# FIT_CONN.net
KiCad netlist of a schematic drawn in Altium Designer
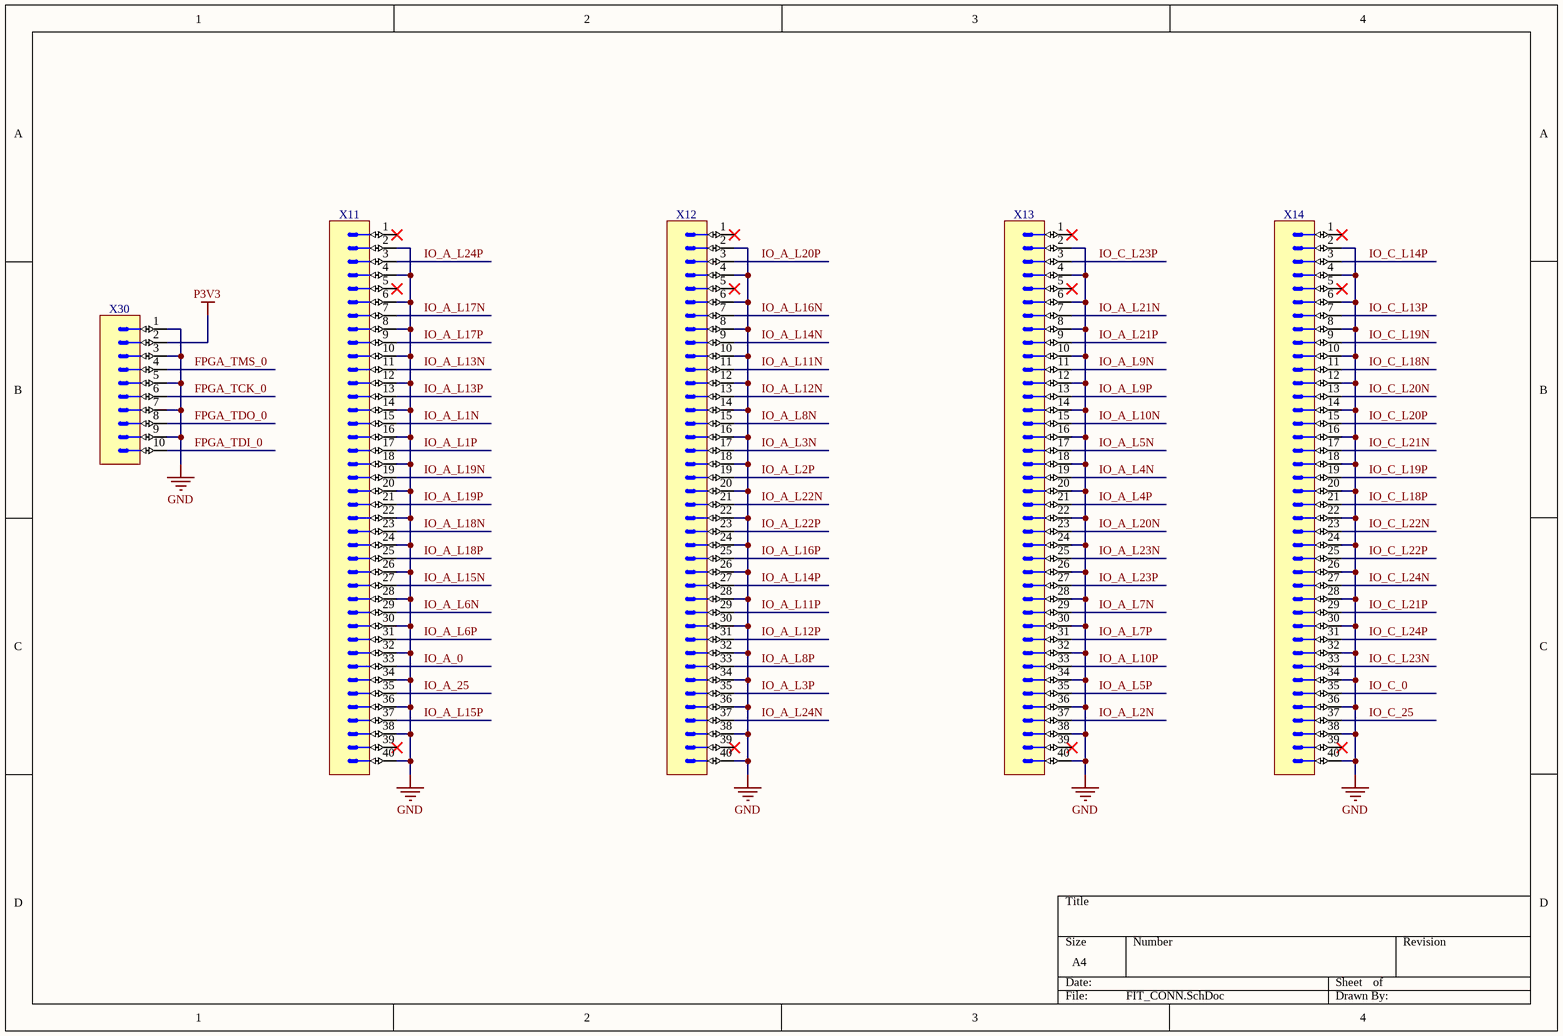
[diagram p0: FIT_CONN.SchDoc]

(export (version "E")
  (design (tool "Eeschema 10.0.6"))
  (components
    (comp (ref "X11")
      (value "~")
      (footprint "CONNFLY_DS1013-40SSIB1-B-0")
      (description "Connector 40 Male")
      (fields
        (field (name "PART NUMBER") "CONNFLY_DS1013-40SSIB1-B-0")
        (field (name "MANUFACTURER") "CONNFLY")
        (field (name "AUTHOR") "CERN DEM HF")
      )
      (libsource (lib "Connectors") (part "Connector 40 Male"))
    )
    (comp (ref "X12")
      (value "~")
      (footprint "CONNFLY_DS1013-40SSIB1-B-0")
      (description "Connector 40 Male")
      (fields
        (field (name "PART NUMBER") "CONNFLY_DS1013-40SSIB1-B-0")
        (field (name "MANUFACTURER") "CONNFLY")
        (field (name "AUTHOR") "CERN DEM HF")
      )
      (libsource (lib "Connectors") (part "Connector 40 Male"))
    )
    (comp (ref "X13")
      (value "~")
      (footprint "CONNFLY_DS1013-40SSIB1-B-0")
      (description "Connector 40 Male")
      (fields
        (field (name "PART NUMBER") "CONNFLY_DS1013-40SSIB1-B-0")
        (field (name "MANUFACTURER") "CONNFLY")
        (field (name "AUTHOR") "CERN DEM HF")
      )
      (libsource (lib "Connectors") (part "Connector 40 Male"))
    )
    (comp (ref "X14")
      (value "~")
      (footprint "CONNFLY_DS1013-40SSIB1-B-0")
      (description "Connector 40 Male")
      (fields
        (field (name "PART NUMBER") "CONNFLY_DS1013-40SSIB1-B-0")
        (field (name "MANUFACTURER") "CONNFLY")
        (field (name "AUTHOR") "CERN DEM HF")
      )
      (libsource (lib "Connectors") (part "Connector 40 Male"))
    )
    (comp (ref "X30")
      (value "~")
      (footprint "CONNFLY_DS1014-10SF1B-B")
      (description "Connector 10 Male")
      (fields
        (field (name "PART NUMBER") "CONNFLY_DS1014-10SF1B-B")
        (field (name "MANUFACTURER") "CONNFLY")
        (field (name "AUTHOR") "CERN DEM HF")
      )
      (libsource (lib "Connectors") (part "Connector 10 Male"))
    )
  )
  (nets
    (net (code "1") (name "/FPGA_TCK_0") (class "Default")
      (node (ref "X30") (pin "6") (pinfunction "6_6") (pintype "bidirectional"))
    )
    (net (code "2") (name "/FPGA_TDI_0") (class "Default")
      (node (ref "X30") (pin "10") (pinfunction "10_10") (pintype "bidirectional"))
    )
    (net (code "3") (name "/FPGA_TDO_0") (class "Default")
      (node (ref "X30") (pin "8") (pinfunction "8_8") (pintype "bidirectional"))
    )
    (net (code "4") (name "/FPGA_TMS_0") (class "Default")
      (node (ref "X30") (pin "4") (pinfunction "4_4") (pintype "bidirectional"))
    )
    (net (code "5") (name "/IO_A_0") (class "Default")
      (node (ref "X11") (pin "33") (pinfunction "33_33") (pintype "bidirectional"))
    )
    (net (code "6") (name "/IO_A_25") (class "Default")
      (node (ref "X11") (pin "35") (pinfunction "35_35") (pintype "bidirectional"))
    )
    (net (code "7") (name "/IO_A_L1N") (class "Default")
      (node (ref "X11") (pin "15") (pinfunction "15_15") (pintype "bidirectional"))
    )
    (net (code "8") (name "/IO_A_L1P") (class "Default")
      (node (ref "X11") (pin "17") (pinfunction "17_17") (pintype "bidirectional"))
    )
    (net (code "9") (name "/IO_A_L2N") (class "Default")
      (node (ref "X13") (pin "37") (pinfunction "37_37") (pintype "bidirectional"))
    )
    (net (code "10") (name "/IO_A_L2P") (class "Default")
      (node (ref "X12") (pin "19") (pinfunction "19_19") (pintype "bidirectional"))
    )
    (net (code "11") (name "/IO_A_L3N") (class "Default")
      (node (ref "X12") (pin "17") (pinfunction "17_17") (pintype "bidirectional"))
    )
    (net (code "12") (name "/IO_A_L3P") (class "Default")
      (node (ref "X12") (pin "35") (pinfunction "35_35") (pintype "bidirectional"))
    )
    (net (code "13") (name "/IO_A_L4N") (class "Default")
      (node (ref "X13") (pin "19") (pinfunction "19_19") (pintype "bidirectional"))
    )
    (net (code "14") (name "/IO_A_L4P") (class "Default")
      (node (ref "X13") (pin "21") (pinfunction "21_21") (pintype "bidirectional"))
    )
    (net (code "15") (name "/IO_A_L5N") (class "Default")
      (node (ref "X13") (pin "17") (pinfunction "17_17") (pintype "bidirectional"))
    )
    (net (code "16") (name "/IO_A_L5P") (class "Default")
      (node (ref "X13") (pin "35") (pinfunction "35_35") (pintype "bidirectional"))
    )
    (net (code "17") (name "/IO_A_L6N") (class "Default")
      (node (ref "X11") (pin "29") (pinfunction "29_29") (pintype "bidirectional"))
    )
    (net (code "18") (name "/IO_A_L6P") (class "Default")
      (node (ref "X11") (pin "31") (pinfunction "31_31") (pintype "bidirectional"))
    )
    (net (code "19") (name "/IO_A_L7N") (class "Default")
      (node (ref "X13") (pin "29") (pinfunction "29_29") (pintype "bidirectional"))
    )
    (net (code "20") (name "/IO_A_L7P") (class "Default")
      (node (ref "X13") (pin "31") (pinfunction "31_31") (pintype "bidirectional"))
    )
    (net (code "21") (name "/IO_A_L8N") (class "Default")
      (node (ref "X12") (pin "15") (pinfunction "15_15") (pintype "bidirectional"))
    )
    (net (code "22") (name "/IO_A_L8P") (class "Default")
      (node (ref "X12") (pin "33") (pinfunction "33_33") (pintype "bidirectional"))
    )
    (net (code "23") (name "/IO_A_L9N") (class "Default")
      (node (ref "X13") (pin "11") (pinfunction "11_11") (pintype "bidirectional"))
    )
    (net (code "24") (name "/IO_A_L9P") (class "Default")
      (node (ref "X13") (pin "13") (pinfunction "13_13") (pintype "bidirectional"))
    )
    (net (code "25") (name "/IO_A_L10N") (class "Default")
      (node (ref "X13") (pin "15") (pinfunction "15_15") (pintype "bidirectional"))
    )
    (net (code "26") (name "/IO_A_L10P") (class "Default")
      (node (ref "X13") (pin "33") (pinfunction "33_33") (pintype "bidirectional"))
    )
    (net (code "27") (name "/IO_A_L11N") (class "Default")
      (node (ref "X12") (pin "11") (pinfunction "11_11") (pintype "bidirectional"))
    )
    (net (code "28") (name "/IO_A_L11P") (class "Default")
      (node (ref "X12") (pin "29") (pinfunction "29_29") (pintype "bidirectional"))
    )
    (net (code "29") (name "/IO_A_L12N") (class "Default")
      (node (ref "X12") (pin "13") (pinfunction "13_13") (pintype "bidirectional"))
    )
    (net (code "30") (name "/IO_A_L12P") (class "Default")
      (node (ref "X12") (pin "31") (pinfunction "31_31") (pintype "bidirectional"))
    )
    (net (code "31") (name "/IO_A_L13N") (class "Default")
      (node (ref "X11") (pin "11") (pinfunction "11_11") (pintype "bidirectional"))
    )
    (net (code "32") (name "/IO_A_L13P") (class "Default")
      (node (ref "X11") (pin "13") (pinfunction "13_13") (pintype "bidirectional"))
    )
    (net (code "33") (name "/IO_A_L14N") (class "Default")
      (node (ref "X12") (pin "9") (pinfunction "9_9") (pintype "bidirectional"))
    )
    (net (code "34") (name "/IO_A_L14P") (class "Default")
      (node (ref "X12") (pin "27") (pinfunction "27_27") (pintype "bidirectional"))
    )
    (net (code "35") (name "/IO_A_L15N") (class "Default")
      (node (ref "X11") (pin "27") (pinfunction "27_27") (pintype "bidirectional"))
    )
    (net (code "36") (name "/IO_A_L15P") (class "Default")
      (node (ref "X11") (pin "37") (pinfunction "37_37") (pintype "bidirectional"))
    )
    (net (code "37") (name "/IO_A_L16N") (class "Default")
      (node (ref "X12") (pin "7") (pinfunction "7_7") (pintype "bidirectional"))
    )
    (net (code "38") (name "/IO_A_L16P") (class "Default")
      (node (ref "X12") (pin "25") (pinfunction "25_25") (pintype "bidirectional"))
    )
    (net (code "39") (name "/IO_A_L17N") (class "Default")
      (node (ref "X11") (pin "7") (pinfunction "7_7") (pintype "bidirectional"))
    )
    (net (code "40") (name "/IO_A_L17P") (class "Default")
      (node (ref "X11") (pin "9") (pinfunction "9_9") (pintype "bidirectional"))
    )
    (net (code "41") (name "/IO_A_L18N") (class "Default")
      (node (ref "X11") (pin "23") (pinfunction "23_23") (pintype "bidirectional"))
    )
    (net (code "42") (name "/IO_A_L18P") (class "Default")
      (node (ref "X11") (pin "25") (pinfunction "25_25") (pintype "bidirectional"))
    )
    (net (code "43") (name "/IO_A_L19N") (class "Default")
      (node (ref "X11") (pin "19") (pinfunction "19_19") (pintype "bidirectional"))
    )
    (net (code "44") (name "/IO_A_L19P") (class "Default")
      (node (ref "X11") (pin "21") (pinfunction "21_21") (pintype "bidirectional"))
    )
    (net (code "45") (name "/IO_A_L20N") (class "Default")
      (node (ref "X13") (pin "23") (pinfunction "23_23") (pintype "bidirectional"))
    )
    (net (code "46") (name "/IO_A_L20P") (class "Default")
      (node (ref "X12") (pin "3") (pinfunction "3_3") (pintype "bidirectional"))
    )
    (net (code "47") (name "/IO_A_L21N") (class "Default")
      (node (ref "X13") (pin "7") (pinfunction "7_7") (pintype "bidirectional"))
    )
    (net (code "48") (name "/IO_A_L21P") (class "Default")
      (node (ref "X13") (pin "9") (pinfunction "9_9") (pintype "bidirectional"))
    )
    (net (code "49") (name "/IO_A_L22N") (class "Default")
      (node (ref "X12") (pin "21") (pinfunction "21_21") (pintype "bidirectional"))
    )
    (net (code "50") (name "/IO_A_L22P") (class "Default")
      (node (ref "X12") (pin "23") (pinfunction "23_23") (pintype "bidirectional"))
    )
    (net (code "51") (name "/IO_A_L23N") (class "Default")
      (node (ref "X13") (pin "25") (pinfunction "25_25") (pintype "bidirectional"))
    )
    (net (code "52") (name "/IO_A_L23P") (class "Default")
      (node (ref "X13") (pin "27") (pinfunction "27_27") (pintype "bidirectional"))
    )
    (net (code "53") (name "/IO_A_L24N") (class "Default")
      (node (ref "X12") (pin "37") (pinfunction "37_37") (pintype "bidirectional"))
    )
    (net (code "54") (name "/IO_A_L24P") (class "Default")
      (node (ref "X11") (pin "3") (pinfunction "3_3") (pintype "bidirectional"))
    )
    (net (code "55") (name "/IO_C_0") (class "Default")
      (node (ref "X14") (pin "35") (pinfunction "35_35") (pintype "bidirectional"))
    )
    (net (code "56") (name "/IO_C_25") (class "Default")
      (node (ref "X14") (pin "37") (pinfunction "37_37") (pintype "bidirectional"))
    )
    (net (code "57") (name "/IO_C_L13P") (class "Default")
      (node (ref "X14") (pin "7") (pinfunction "7_7") (pintype "bidirectional"))
    )
    (net (code "58") (name "/IO_C_L14P") (class "Default")
      (node (ref "X14") (pin "3") (pinfunction "3_3") (pintype "bidirectional"))
    )
    (net (code "59") (name "/IO_C_L18N") (class "Default")
      (node (ref "X14") (pin "11") (pinfunction "11_11") (pintype "bidirectional"))
    )
    (net (code "60") (name "/IO_C_L18P") (class "Default")
      (node (ref "X14") (pin "21") (pinfunction "21_21") (pintype "bidirectional"))
    )
    (net (code "61") (name "/IO_C_L19N") (class "Default")
      (node (ref "X14") (pin "9") (pinfunction "9_9") (pintype "bidirectional"))
    )
    (net (code "62") (name "/IO_C_L19P") (class "Default")
      (node (ref "X14") (pin "19") (pinfunction "19_19") (pintype "bidirectional"))
    )
    (net (code "63") (name "/IO_C_L20N") (class "Default")
      (node (ref "X14") (pin "13") (pinfunction "13_13") (pintype "bidirectional"))
    )
    (net (code "64") (name "/IO_C_L20P") (class "Default")
      (node (ref "X14") (pin "15") (pinfunction "15_15") (pintype "bidirectional"))
    )
    (net (code "65") (name "/IO_C_L21N") (class "Default")
      (node (ref "X14") (pin "17") (pinfunction "17_17") (pintype "bidirectional"))
    )
    (net (code "66") (name "/IO_C_L21P") (class "Default")
      (node (ref "X14") (pin "29") (pinfunction "29_29") (pintype "bidirectional"))
    )
    (net (code "67") (name "/IO_C_L22N") (class "Default")
      (node (ref "X14") (pin "23") (pinfunction "23_23") (pintype "bidirectional"))
    )
    (net (code "68") (name "/IO_C_L22P") (class "Default")
      (node (ref "X14") (pin "25") (pinfunction "25_25") (pintype "bidirectional"))
    )
    (net (code "69") (name "/IO_C_L23N") (class "Default")
      (node (ref "X14") (pin "33") (pinfunction "33_33") (pintype "bidirectional"))
    )
    (net (code "70") (name "/IO_C_L23P") (class "Default")
      (node (ref "X13") (pin "3") (pinfunction "3_3") (pintype "bidirectional"))
    )
    (net (code "71") (name "/IO_C_L24N") (class "Default")
      (node (ref "X14") (pin "27") (pinfunction "27_27") (pintype "bidirectional"))
    )
    (net (code "72") (name "/IO_C_L24P") (class "Default")
      (node (ref "X14") (pin "31") (pinfunction "31_31") (pintype "bidirectional"))
    )
    (net (code "73") (name "GND") (class "Default")
      (node (ref "X11") (pin "10") (pinfunction "10_10") (pintype "bidirectional"))
      (node (ref "X11") (pin "12") (pinfunction "12_12") (pintype "bidirectional"))
      (node (ref "X11") (pin "14") (pinfunction "14_14") (pintype "bidirectional"))
      (node (ref "X11") (pin "16") (pinfunction "16_16") (pintype "bidirectional"))
      (node (ref "X11") (pin "18") (pinfunction "18_18") (pintype "bidirectional"))
      (node (ref "X11") (pin "2") (pinfunction "2_2") (pintype "bidirectional"))
      (node (ref "X11") (pin "20") (pinfunction "20_20") (pintype "bidirectional"))
      (node (ref "X11") (pin "22") (pinfunction "22_22") (pintype "bidirectional"))
      (node (ref "X11") (pin "24") (pinfunction "24_24") (pintype "bidirectional"))
      (node (ref "X11") (pin "26") (pinfunction "26_26") (pintype "bidirectional"))
      (node (ref "X11") (pin "28") (pinfunction "28_28") (pintype "bidirectional"))
      (node (ref "X11") (pin "30") (pinfunction "30_30") (pintype "bidirectional"))
      (node (ref "X11") (pin "32") (pinfunction "32_32") (pintype "bidirectional"))
      (node (ref "X11") (pin "34") (pinfunction "34_34") (pintype "bidirectional"))
      (node (ref "X11") (pin "36") (pinfunction "36_36") (pintype "bidirectional"))
      (node (ref "X11") (pin "38") (pinfunction "38_38") (pintype "bidirectional"))
      (node (ref "X11") (pin "4") (pinfunction "4_4") (pintype "bidirectional"))
      (node (ref "X11") (pin "40") (pinfunction "40_40") (pintype "bidirectional"))
      (node (ref "X11") (pin "6") (pinfunction "6_6") (pintype "bidirectional"))
      (node (ref "X11") (pin "8") (pinfunction "8_8") (pintype "bidirectional"))
      (node (ref "X12") (pin "10") (pinfunction "10_10") (pintype "bidirectional"))
      (node (ref "X12") (pin "12") (pinfunction "12_12") (pintype "bidirectional"))
      (node (ref "X12") (pin "14") (pinfunction "14_14") (pintype "bidirectional"))
      (node (ref "X12") (pin "16") (pinfunction "16_16") (pintype "bidirectional"))
      (node (ref "X12") (pin "18") (pinfunction "18_18") (pintype "bidirectional"))
      (node (ref "X12") (pin "2") (pinfunction "2_2") (pintype "bidirectional"))
      (node (ref "X12") (pin "20") (pinfunction "20_20") (pintype "bidirectional"))
      (node (ref "X12") (pin "22") (pinfunction "22_22") (pintype "bidirectional"))
      (node (ref "X12") (pin "24") (pinfunction "24_24") (pintype "bidirectional"))
      (node (ref "X12") (pin "26") (pinfunction "26_26") (pintype "bidirectional"))
      (node (ref "X12") (pin "28") (pinfunction "28_28") (pintype "bidirectional"))
      (node (ref "X12") (pin "30") (pinfunction "30_30") (pintype "bidirectional"))
      (node (ref "X12") (pin "32") (pinfunction "32_32") (pintype "bidirectional"))
      (node (ref "X12") (pin "34") (pinfunction "34_34") (pintype "bidirectional"))
      (node (ref "X12") (pin "36") (pinfunction "36_36") (pintype "bidirectional"))
      (node (ref "X12") (pin "38") (pinfunction "38_38") (pintype "bidirectional"))
      (node (ref "X12") (pin "4") (pinfunction "4_4") (pintype "bidirectional"))
      (node (ref "X12") (pin "40") (pinfunction "40_40") (pintype "bidirectional"))
      (node (ref "X12") (pin "6") (pinfunction "6_6") (pintype "bidirectional"))
      (node (ref "X12") (pin "8") (pinfunction "8_8") (pintype "bidirectional"))
      (node (ref "X13") (pin "10") (pinfunction "10_10") (pintype "bidirectional"))
      (node (ref "X13") (pin "12") (pinfunction "12_12") (pintype "bidirectional"))
      (node (ref "X13") (pin "14") (pinfunction "14_14") (pintype "bidirectional"))
      (node (ref "X13") (pin "16") (pinfunction "16_16") (pintype "bidirectional"))
      (node (ref "X13") (pin "18") (pinfunction "18_18") (pintype "bidirectional"))
      (node (ref "X13") (pin "2") (pinfunction "2_2") (pintype "bidirectional"))
      (node (ref "X13") (pin "20") (pinfunction "20_20") (pintype "bidirectional"))
      (node (ref "X13") (pin "22") (pinfunction "22_22") (pintype "bidirectional"))
      (node (ref "X13") (pin "24") (pinfunction "24_24") (pintype "bidirectional"))
      (node (ref "X13") (pin "26") (pinfunction "26_26") (pintype "bidirectional"))
      (node (ref "X13") (pin "28") (pinfunction "28_28") (pintype "bidirectional"))
      (node (ref "X13") (pin "30") (pinfunction "30_30") (pintype "bidirectional"))
      (node (ref "X13") (pin "32") (pinfunction "32_32") (pintype "bidirectional"))
      (node (ref "X13") (pin "34") (pinfunction "34_34") (pintype "bidirectional"))
      (node (ref "X13") (pin "36") (pinfunction "36_36") (pintype "bidirectional"))
      (node (ref "X13") (pin "38") (pinfunction "38_38") (pintype "bidirectional"))
      (node (ref "X13") (pin "4") (pinfunction "4_4") (pintype "bidirectional"))
      (node (ref "X13") (pin "40") (pinfunction "40_40") (pintype "bidirectional"))
      (node (ref "X13") (pin "6") (pinfunction "6_6") (pintype "bidirectional"))
      (node (ref "X13") (pin "8") (pinfunction "8_8") (pintype "bidirectional"))
      (node (ref "X14") (pin "10") (pinfunction "10_10") (pintype "bidirectional"))
      (node (ref "X14") (pin "12") (pinfunction "12_12") (pintype "bidirectional"))
      (node (ref "X14") (pin "14") (pinfunction "14_14") (pintype "bidirectional"))
      (node (ref "X14") (pin "16") (pinfunction "16_16") (pintype "bidirectional"))
      (node (ref "X14") (pin "18") (pinfunction "18_18") (pintype "bidirectional"))
      (node (ref "X14") (pin "2") (pinfunction "2_2") (pintype "bidirectional"))
      (node (ref "X14") (pin "20") (pinfunction "20_20") (pintype "bidirectional"))
      (node (ref "X14") (pin "22") (pinfunction "22_22") (pintype "bidirectional"))
      (node (ref "X14") (pin "24") (pinfunction "24_24") (pintype "bidirectional"))
      (node (ref "X14") (pin "26") (pinfunction "26_26") (pintype "bidirectional"))
      (node (ref "X14") (pin "28") (pinfunction "28_28") (pintype "bidirectional"))
      (node (ref "X14") (pin "30") (pinfunction "30_30") (pintype "bidirectional"))
      (node (ref "X14") (pin "32") (pinfunction "32_32") (pintype "bidirectional"))
      (node (ref "X14") (pin "34") (pinfunction "34_34") (pintype "bidirectional"))
      (node (ref "X14") (pin "36") (pinfunction "36_36") (pintype "bidirectional"))
      (node (ref "X14") (pin "38") (pinfunction "38_38") (pintype "bidirectional"))
      (node (ref "X14") (pin "4") (pinfunction "4_4") (pintype "bidirectional"))
      (node (ref "X14") (pin "40") (pinfunction "40_40") (pintype "bidirectional"))
      (node (ref "X14") (pin "6") (pinfunction "6_6") (pintype "bidirectional"))
      (node (ref "X14") (pin "8") (pinfunction "8_8") (pintype "bidirectional"))
      (node (ref "X30") (pin "1") (pinfunction "1_1") (pintype "bidirectional"))
      (node (ref "X30") (pin "3") (pinfunction "3_3") (pintype "bidirectional"))
      (node (ref "X30") (pin "5") (pinfunction "5_5") (pintype "bidirectional"))
      (node (ref "X30") (pin "7") (pinfunction "7_7") (pintype "bidirectional"))
      (node (ref "X30") (pin "9") (pinfunction "9_9") (pintype "bidirectional"))
    )
    (net (code "74") (name "P3V3") (class "Default")
      (node (ref "X30") (pin "2") (pinfunction "2_2") (pintype "bidirectional"))
    )
    (net (code "75") (name "unconnected-(X11-Pad1)") (class "Default")
      (node (ref "X11") (pin "1") (pinfunction "1_1") (pintype "bidirectional+no_connect"))
    )
    (net (code "76") (name "unconnected-(X11-Pad5)") (class "Default")
      (node (ref "X11") (pin "5") (pinfunction "5_5") (pintype "bidirectional+no_connect"))
    )
    (net (code "77") (name "unconnected-(X11-Pad39)") (class "Default")
      (node (ref "X11") (pin "39") (pinfunction "39_39") (pintype "bidirectional+no_connect"))
    )
    (net (code "78") (name "unconnected-(X12-Pad1)") (class "Default")
      (node (ref "X12") (pin "1") (pinfunction "1_1") (pintype "bidirectional+no_connect"))
    )
    (net (code "79") (name "unconnected-(X12-Pad5)") (class "Default")
      (node (ref "X12") (pin "5") (pinfunction "5_5") (pintype "bidirectional+no_connect"))
    )
    (net (code "80") (name "unconnected-(X12-Pad39)") (class "Default")
      (node (ref "X12") (pin "39") (pinfunction "39_39") (pintype "bidirectional+no_connect"))
    )
    (net (code "81") (name "unconnected-(X13-Pad1)") (class "Default")
      (node (ref "X13") (pin "1") (pinfunction "1_1") (pintype "bidirectional+no_connect"))
    )
    (net (code "82") (name "unconnected-(X13-Pad5)") (class "Default")
      (node (ref "X13") (pin "5") (pinfunction "5_5") (pintype "bidirectional+no_connect"))
    )
    (net (code "83") (name "unconnected-(X13-Pad39)") (class "Default")
      (node (ref "X13") (pin "39") (pinfunction "39_39") (pintype "bidirectional+no_connect"))
    )
    (net (code "84") (name "unconnected-(X14-Pad1)") (class "Default")
      (node (ref "X14") (pin "1") (pinfunction "1_1") (pintype "bidirectional+no_connect"))
    )
    (net (code "85") (name "unconnected-(X14-Pad5)") (class "Default")
      (node (ref "X14") (pin "5") (pinfunction "5_5") (pintype "bidirectional+no_connect"))
    )
    (net (code "86") (name "unconnected-(X14-Pad39)") (class "Default")
      (node (ref "X14") (pin "39") (pinfunction "39_39") (pintype "bidirectional+no_connect"))
    )
  )
)
